# Slave.net
KiCad netlist of a schematic drawn in EAGLE
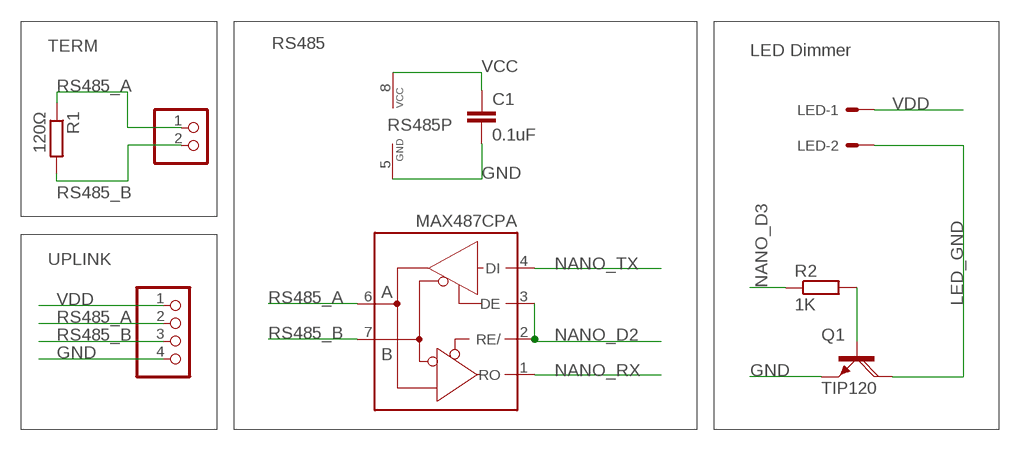
[diagram p0: schematic, sheet 1]

(export (version "E")
  (design (tool "Eeschema 10.0.6"))
  (components
    (comp (ref "C1")
      (value "0.1uF")
      (footprint "eagle-import:C025-025X050")
      (libsource (lib "eagle-import") (part "C-EU025-025X050"))
    )
    (comp (ref "LED")
      (value "KK-156-2")
      (footprint "eagle-import:KK-156-2")
      (fields (field (name "MF") "MOLEX"))
      (libsource (lib "eagle-import") (part "KK-156-2"))
    )
    (comp (ref "Q1")
      (value "TIP120")
      (footprint "eagle-import:TO220AH")
      (libsource (lib "eagle-import") (part "TIP120"))
    )
    (comp (ref "R1")
      (value "120Ω")
      (footprint "eagle-import:0207_10")
      (libsource (lib "eagle-import") (part "R-EU_0207/10"))
    )
    (comp (ref "R2")
      (value "1K")
      (footprint "eagle-import:0207_10")
      (libsource (lib "eagle-import") (part "R-EU_0207/10"))
    )
    (comp (ref "RS485")
      (value "MAX487CPA")
      (footprint "eagle-import:DIL08")
      (libsource (lib "eagle-import") (part "MAX487CPA"))
    )
    (comp (ref "TERM")
      (value "PINHD-1X2")
      (footprint "eagle-import:1X02")
      (libsource (lib "eagle-import") (part "PINHD-1X2"))
    )
    (comp (ref "UPLINK")
      (value "PINHD-1X4")
      (footprint "eagle-import:1X04")
      (libsource (lib "eagle-import") (part "PINHD-1X4"))
    )
  )
  (nets
    (net (code "1") (name "/GND") (class "Default")
      (node (ref "C1") (pin "2") (pinfunction "2_2") (pintype "passive"))
      (node (ref "Q1") (pin "E") (pinfunction "E_E") (pintype "passive"))
      (node (ref "RS485") (pin "5") (pinfunction "GND_5") (pintype "power_in"))
      (node (ref "UPLINK") (pin "4") (pinfunction "4_4") (pintype "passive"))
    )
    (net (code "2") (name "/LED_GND") (class "Default")
      (node (ref "LED") (pin "2") (pinfunction "S_2") (pintype "passive"))
      (node (ref "Q1") (pin "C") (pinfunction "C_C") (pintype "passive"))
    )
    (net (code "3") (name "/NANO_D2") (class "Default")
      (node (ref "RS485") (pin "2") (pinfunction "RE/_2") (pintype "input"))
      (node (ref "RS485") (pin "3") (pinfunction "DE_3") (pintype "input"))
    )
    (net (code "4") (name "/NANO_D3") (class "Default")
      (node (ref "R2") (pin "1") (pinfunction "1_1") (pintype "passive"))
    )
    (net (code "5") (name "/NANO_RX") (class "Default")
      (node (ref "RS485") (pin "1") (pinfunction "RO_1") (pintype "output"))
    )
    (net (code "6") (name "/NANO_TX") (class "Default")
      (node (ref "RS485") (pin "4") (pinfunction "DI_4") (pintype "input"))
    )
    (net (code "7") (name "/RS485_A") (class "Default")
      (node (ref "R1") (pin "1") (pinfunction "1_1") (pintype "passive"))
      (node (ref "RS485") (pin "6") (pinfunction "A_6") (pintype "passive"))
      (node (ref "TERM") (pin "1") (pinfunction "1_1") (pintype "passive"))
      (node (ref "UPLINK") (pin "2") (pinfunction "2_2") (pintype "passive"))
    )
    (net (code "8") (name "/RS485_B") (class "Default")
      (node (ref "R1") (pin "2") (pinfunction "2_2") (pintype "passive"))
      (node (ref "RS485") (pin "7") (pinfunction "B_7") (pintype "passive"))
      (node (ref "TERM") (pin "2") (pinfunction "2_2") (pintype "passive"))
      (node (ref "UPLINK") (pin "3") (pinfunction "3_3") (pintype "passive"))
    )
    (net (code "9") (name "/VCC") (class "Default")
      (node (ref "C1") (pin "1") (pinfunction "1_1") (pintype "passive"))
      (node (ref "RS485") (pin "8") (pinfunction "VCC_8") (pintype "power_in"))
    )
    (net (code "10") (name "/VDD") (class "Default")
      (node (ref "LED") (pin "1") (pinfunction "S_1") (pintype "passive"))
      (node (ref "UPLINK") (pin "1") (pinfunction "1_1") (pintype "passive"))
    )
    (net (code "11") (name "Net-(Q1-PadB)") (class "Default")
      (node (ref "Q1") (pin "B") (pinfunction "B_B") (pintype "passive"))
      (node (ref "R2") (pin "2") (pinfunction "2_2") (pintype "passive"))
    )
  )
)
